# Circuito.net
KiCad netlist of a schematic drawn in Altium Designer
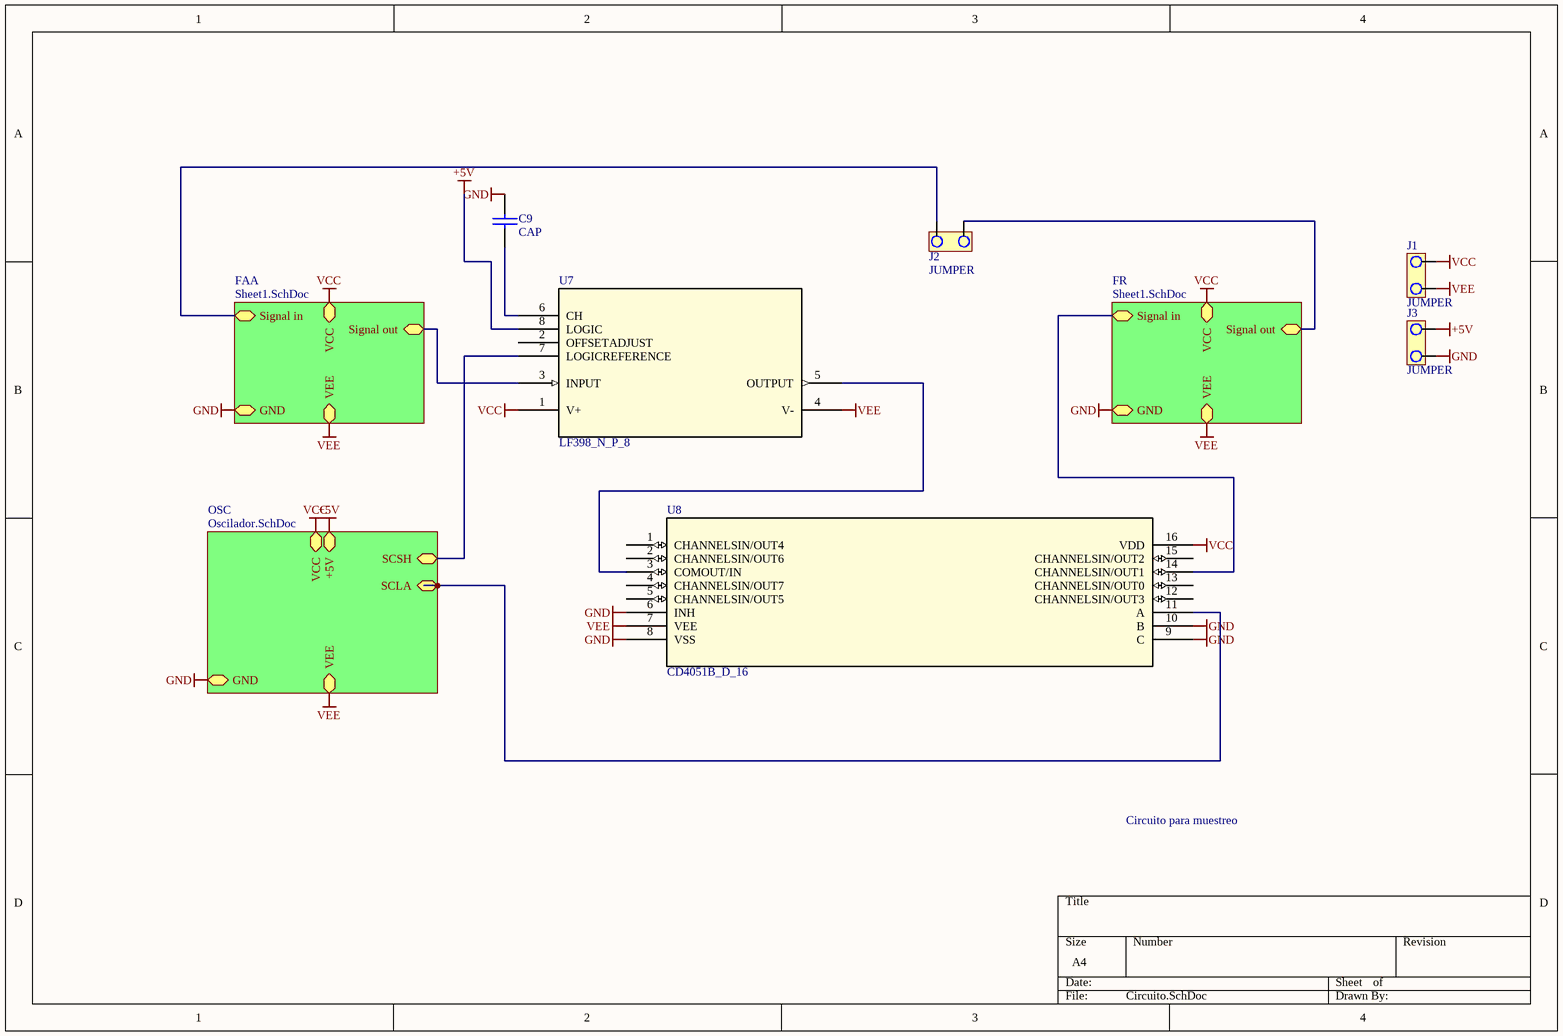
[diagram p0: Circuito.SchDoc]

(export (version "E")
  (design (tool "Eeschema 10.0.6"))
  (components
    (comp (ref "C9") (value "CAP") (footprint "CAP100") (libsource (lib "LIBEBAL") (part "CAP")))
    (comp (ref "J1") (value "JUMPER") (footprint "JUMPER2") (libsource (lib "") (part "JUMPER_1")))
    (comp (ref "J2") (value "JUMPER") (footprint "JUMPER2") (libsource (lib "LIBEBAL") (part "JUMPER")))
    (comp (ref "J3") (value "JUMPER") (footprint "JUMPER2") (libsource (lib "") (part "JUMPER_1")))
    (comp (ref "U7")
      (value "LF398_N_P_8")
      (footprint "P8")
      (description "Imported")
      (fields (field (name "MANUFACTURER_PART_NUMBER") "lf398-n_p_8"))
      (libsource (lib "2020-04-06_20-05-45") (part "LF398_N_P_8"))
    )
    (comp (ref "U8")
      (value "CD4051B_D_16")
      (footprint "D16")
      (description "Imported")
      (fields
        (field (name "MANUFACTURER") "Texas Instruments")
        (field (name "GENERIC_PART_NUMBER") "CD4051B")
      )
      (libsource (lib "2020-04-06_20-25-18") (part "CD4051B_D_16"))
    )
  )
  (nets
    (net (code "1") (name "+5V") (class "Default")
      (node (ref "J3") (pin "1") (pinfunction "1_1") (pintype "passive"))
      (node (ref "U7") (pin "8") (pinfunction "LOGIC_8") (pintype "passive"))
    )
    (net (code "2") (name "/SCLA") (class "Default")
      (node (ref "U8") (pin "11") (pinfunction "A_11") (pintype "passive"))
    )
    (net (code "3") (name "/SCSH") (class "Default")
      (node (ref "U7") (pin "7") (pinfunction "LOGICREFERENCE_7") (pintype "passive"))
    )
    (net (code "4") (name "/Signal in") (class "Default")
      (node (ref "J2") (pin "1") (pinfunction "1_1") (pintype "passive"))
    )
    (net (code "5") (name "/Signal in_1") (class "Default")
      (node (ref "U8") (pin "14") (pinfunction "CHANNELSIN/OUT1_14") (pintype "bidirectional"))
    )
    (net (code "6") (name "/Signal out") (class "Default")
      (node (ref "J2") (pin "2") (pinfunction "2_2") (pintype "passive"))
    )
    (net (code "7") (name "/Signal out_1") (class "Default")
      (node (ref "U7") (pin "3") (pinfunction "INPUT_3") (pintype "input"))
    )
    (net (code "8") (name "GND") (class "Default")
      (node (ref "C9") (pin "1") (pinfunction "1_1") (pintype "passive"))
      (node (ref "J3") (pin "2") (pinfunction "2_2") (pintype "passive"))
      (node (ref "U8") (pin "10") (pinfunction "B_10") (pintype "passive"))
      (node (ref "U8") (pin "6") (pinfunction "INH_6") (pintype "passive"))
      (node (ref "U8") (pin "8") (pinfunction "VSS_8") (pintype "power_in"))
      (node (ref "U8") (pin "9") (pinfunction "C_9") (pintype "passive"))
    )
    (net (code "9") (name "Net-(U7-CH)") (class "Default")
      (node (ref "C9") (pin "2") (pinfunction "2_2") (pintype "passive"))
      (node (ref "U7") (pin "6") (pinfunction "CH_6") (pintype "passive"))
    )
    (net (code "10") (name "Net-(U7-OUTPUT)") (class "Default")
      (node (ref "U7") (pin "5") (pinfunction "OUTPUT_5") (pintype "output"))
      (node (ref "U8") (pin "3") (pinfunction "COMOUT/IN_3") (pintype "bidirectional"))
    )
    (net (code "11") (name "VCC") (class "Default")
      (node (ref "J1") (pin "1") (pinfunction "1_1") (pintype "passive"))
      (node (ref "U7") (pin "1") (pinfunction "V+_1") (pintype "power_in"))
      (node (ref "U8") (pin "16") (pinfunction "VDD_16") (pintype "power_in"))
    )
    (net (code "12") (name "VEE") (class "Default")
      (node (ref "J1") (pin "2") (pinfunction "2_2") (pintype "passive"))
      (node (ref "U7") (pin "4") (pinfunction "V-_4") (pintype "power_in"))
      (node (ref "U8") (pin "7") (pinfunction "VEE_7") (pintype "power_in"))
    )
    (net (code "13") (name "unconnected-(U7-OFFSETADJUST-Pad2)") (class "Default")
      (node (ref "U7") (pin "2") (pinfunction "OFFSETADJUST_2") (pintype "passive"))
    )
    (net (code "14") (name "unconnected-(U8-CHANNELSIN{slash}OUT0-Pad13)") (class "Default")
      (node (ref "U8") (pin "13") (pinfunction "CHANNELSIN/OUT0_13") (pintype "bidirectional"))
    )
    (net (code "15") (name "unconnected-(U8-CHANNELSIN{slash}OUT2-Pad15)") (class "Default")
      (node (ref "U8") (pin "15") (pinfunction "CHANNELSIN/OUT2_15") (pintype "bidirectional"))
    )
    (net (code "16") (name "unconnected-(U8-CHANNELSIN{slash}OUT3-Pad12)") (class "Default")
      (node (ref "U8") (pin "12") (pinfunction "CHANNELSIN/OUT3_12") (pintype "bidirectional"))
    )
    (net (code "17") (name "unconnected-(U8-CHANNELSIN{slash}OUT4-Pad1)") (class "Default")
      (node (ref "U8") (pin "1") (pinfunction "CHANNELSIN/OUT4_1") (pintype "bidirectional"))
    )
    (net (code "18") (name "unconnected-(U8-CHANNELSIN{slash}OUT5-Pad5)") (class "Default")
      (node (ref "U8") (pin "5") (pinfunction "CHANNELSIN/OUT5_5") (pintype "bidirectional"))
    )
    (net (code "19") (name "unconnected-(U8-CHANNELSIN{slash}OUT6-Pad2)") (class "Default")
      (node (ref "U8") (pin "2") (pinfunction "CHANNELSIN/OUT6_2") (pintype "bidirectional"))
    )
    (net (code "20") (name "unconnected-(U8-CHANNELSIN{slash}OUT7-Pad4)") (class "Default")
      (node (ref "U8") (pin "4") (pinfunction "CHANNELSIN/OUT7_4") (pintype "bidirectional"))
    )
  )
)
